# wind_speed.net
KiCad netlist of a schematic drawn in EAGLE
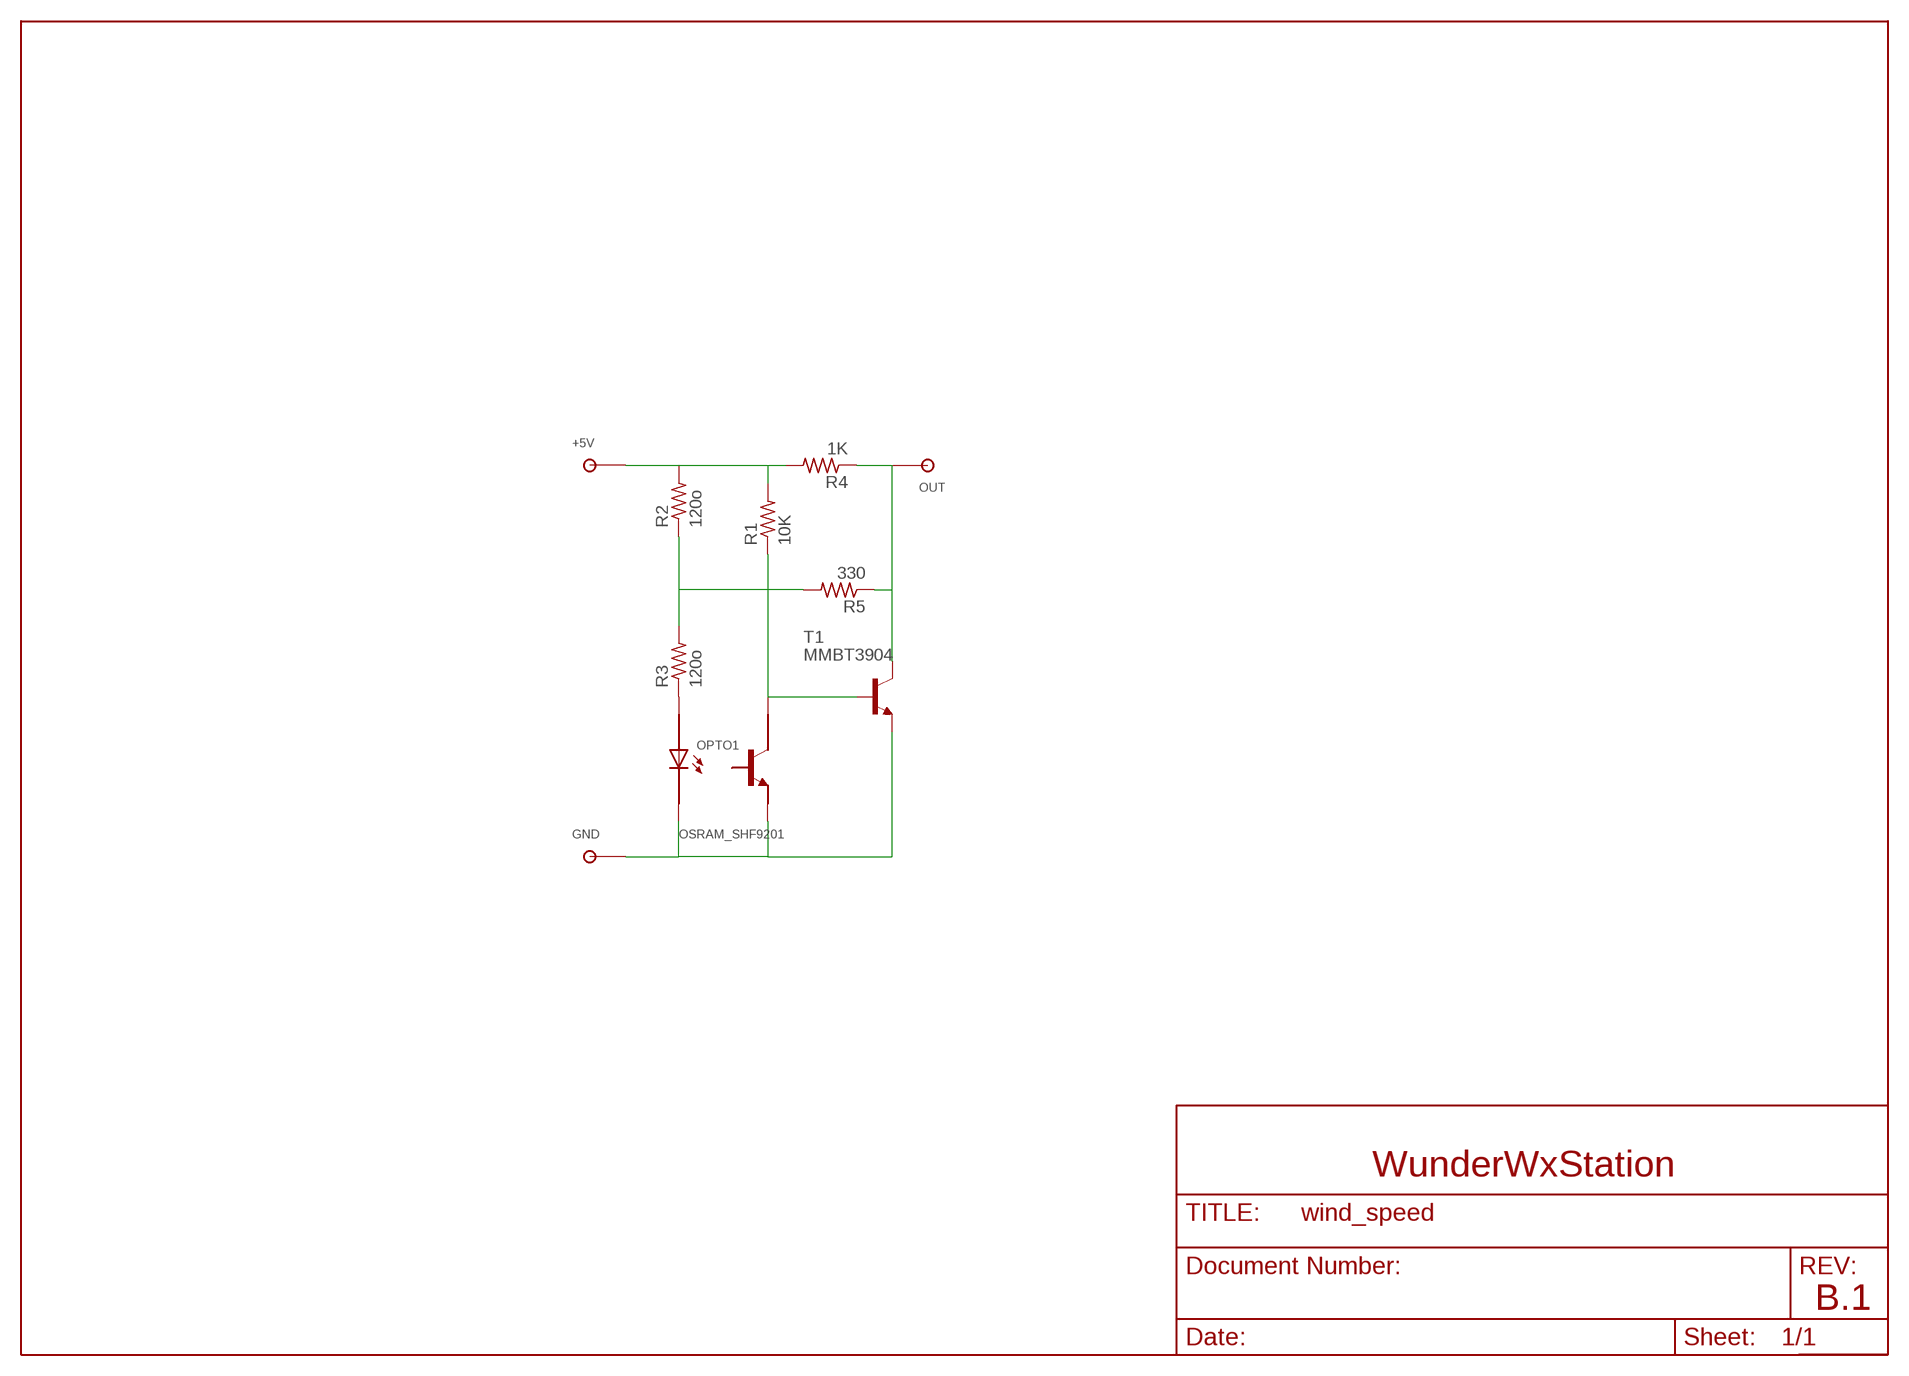
[diagram p0: schematic, sheet 1]

(export (version "E")
  (design (tool "Eeschema 10.0.6"))
  (components
    (comp (ref "+5V")
      (value "TPSOL")
      (footprint "eagle-import:TP_SOL")
      (libsource (lib "eagle-import") (part "TPSOL"))
    )
    (comp (ref "GND")
      (value "TPSOL")
      (footprint "eagle-import:TP_SOL")
      (libsource (lib "eagle-import") (part "TPSOL"))
    )
    (comp (ref "OPTO1")
      (value "OSRAM_SHF9201")
      (footprint "eagle-import:OSRAM-6")
      (libsource (lib "eagle-import") (part "OSRAM_SHF9201"))
    )
    (comp (ref "OUT")
      (value "TPSOL")
      (footprint "eagle-import:TP_SOL")
      (libsource (lib "eagle-import") (part "TPSOL"))
    )
    (comp (ref "R1")
      (value "10K")
      (footprint "eagle-import:R0603")
      (libsource (lib "eagle-import") (part "R-US_R0603"))
    )
    (comp (ref "R2")
      (value "120o")
      (footprint "eagle-import:R0603")
      (libsource (lib "eagle-import") (part "R-US_R0603"))
    )
    (comp (ref "R3")
      (value "120o")
      (footprint "eagle-import:R0603")
      (libsource (lib "eagle-import") (part "R-US_R0603"))
    )
    (comp (ref "R4")
      (value "1K")
      (footprint "eagle-import:R0603")
      (libsource (lib "eagle-import") (part "R-US_R0603"))
    )
    (comp (ref "R5")
      (value "330")
      (footprint "eagle-import:R0603")
      (libsource (lib "eagle-import") (part "R-US_R0603"))
    )
    (comp (ref "T1")
      (value "MMBT3904")
      (footprint "eagle-import:SOT23")
      (libsource (lib "eagle-import") (part "BC846"))
    )
  )
  (nets
    (net (code "1") (name "Net-(+5V-PadP$1)") (class "Default")
      (node (ref "+5V") (pin "P$1") (pinfunction "P$1_P$1") (pintype "bidirectional"))
      (node (ref "R1") (pin "2") (pinfunction "2_2") (pintype "passive"))
      (node (ref "R2") (pin "2") (pinfunction "2_2") (pintype "passive"))
      (node (ref "R4") (pin "2") (pinfunction "2_2") (pintype "passive"))
    )
    (net (code "2") (name "Net-(OPTO1-AN)") (class "Default")
      (node (ref "OPTO1") (pin "P$1") (pinfunction "AN_P$1") (pintype "passive"))
      (node (ref "R3") (pin "1") (pinfunction "1_1") (pintype "passive"))
    )
    (net (code "3") (name "Net-(OPTO1-C)") (class "Default")
      (node (ref "OPTO1") (pin "P$4") (pinfunction "C_P$4") (pintype "passive"))
      (node (ref "R1") (pin "1") (pinfunction "1_1") (pintype "passive"))
      (node (ref "T1") (pin "1") (pinfunction "B_1") (pintype "passive"))
    )
    (net (code "4") (name "Net-(OPTO1-CATH)") (class "Default")
      (node (ref "GND") (pin "P$1") (pinfunction "P$1_P$1") (pintype "bidirectional"))
      (node (ref "OPTO1") (pin "P$3") (pinfunction "E_P$3") (pintype "passive"))
      (node (ref "OPTO1") (pin "P$6") (pinfunction "CATH_P$6") (pintype "passive"))
      (node (ref "T1") (pin "2") (pinfunction "E_2") (pintype "passive"))
    )
    (net (code "5") (name "Net-(R2-Pad1)") (class "Default")
      (node (ref "R2") (pin "1") (pinfunction "1_1") (pintype "passive"))
      (node (ref "R3") (pin "2") (pinfunction "2_2") (pintype "passive"))
      (node (ref "R5") (pin "2") (pinfunction "2_2") (pintype "passive"))
    )
    (net (code "6") (name "Net-(T1-C)") (class "Default")
      (node (ref "OUT") (pin "P$1") (pinfunction "P$1_P$1") (pintype "bidirectional"))
      (node (ref "R4") (pin "1") (pinfunction "1_1") (pintype "passive"))
      (node (ref "R5") (pin "1") (pinfunction "1_1") (pintype "passive"))
      (node (ref "T1") (pin "3") (pinfunction "C_3") (pintype "passive"))
    )
    (net (code "7") (name "unconnected-(OPTO1-P$2-PadP$5)") (class "Default")
      (node (ref "OPTO1") (pin "P$5") (pinfunction "P$2_P$5") (pintype "no_connect"))
    )
    (net (code "8") (name "unconnected-(OPTO1-P$5-PadP$2)") (class "Default")
      (node (ref "OPTO1") (pin "P$2") (pinfunction "P$5_P$2") (pintype "no_connect"))
    )
  )
)
